# treiber.net
KiCad netlist of a schematic drawn in EAGLE
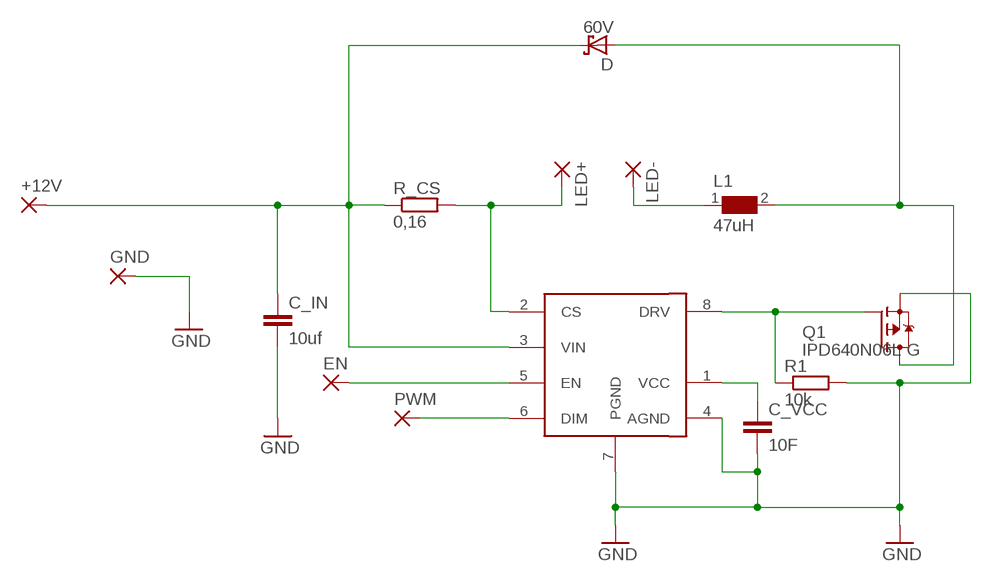
[diagram p0: schematic, sheet 1]

(export (version "E")
  (design (tool "Eeschema 10.0.6"))
  (components
    (comp (ref "+12V")
      (value "WIREPADSMD5-2,5")
      (footprint "eagle-import:5-2,5")
      (libsource (lib "eagle-import") (part "WIREPADSMD5-2,5"))
    )
    (comp (ref "C_IN")
      (value "10uf")
      (footprint "eagle-import:C1210")
      (libsource (lib "eagle-import") (part "C-EUC1210"))
    )
    (comp (ref "C_VCC")
      (value "10F")
      (footprint "eagle-import:C1210")
      (libsource (lib "eagle-import") (part "C-EUC1210"))
    )
    (comp (ref "D")
      (value "60V")
      (footprint "eagle-import:SMC")
      (libsource (lib "eagle-import") (part "SCHOTTKY-DIODESMC"))
    )
    (comp (ref "EN")
      (value "WIREPADSMD5-2,5")
      (footprint "eagle-import:5-2,5")
      (libsource (lib "eagle-import") (part "WIREPADSMD5-2,5"))
    )
    (comp (ref "GND")
      (value "WIREPADSMD5-2,5")
      (footprint "eagle-import:5-2,5")
      (libsource (lib "eagle-import") (part "WIREPADSMD5-2,5"))
    )
    (comp (ref "L1")
      (value "47uH")
      (footprint "eagle-import:WE-TPC_1028_1038")
      (fields (field (name "MPN") "744066680"))
      (libsource (lib "eagle-import") (part "WE-TPC_1028/1038-744066680"))
    )
    (comp (ref "LED+")
      (value "WIREPADSMD5-2,5")
      (footprint "eagle-import:5-2,5")
      (libsource (lib "eagle-import") (part "WIREPADSMD5-2,5"))
    )
    (comp (ref "LED-")
      (value "WIREPADSMD5-2,5")
      (footprint "eagle-import:5-2,5")
      (libsource (lib "eagle-import") (part "WIREPADSMD5-2,5"))
    )
    (comp (ref "MIC3203")
      (value "MIC3203")
      (footprint "eagle-import:SO08")
      (libsource (lib "eagle-import") (part "MIC3203"))
    )
    (comp (ref "PWM")
      (value "WIREPADSMD5-2,5")
      (footprint "eagle-import:5-2,5")
      (libsource (lib "eagle-import") (part "WIREPADSMD5-2,5"))
    )
    (comp (ref "Q1")
      (value "IPD640N06L G")
      (footprint "eagle-import:TO252")
      (libsource (lib "eagle-import") (part "FDD4141TO252"))
    )
    (comp (ref "R1")
      (value "10k")
      (footprint "eagle-import:M1206")
      (libsource (lib "eagle-import") (part "R-EU_M1206"))
    )
    (comp (ref "R_CS")
      (value "0,16")
      (footprint "eagle-import:R0603")
      (libsource (lib "eagle-import") (part "R-EU_R0603"))
    )
  )
  (nets
    (net (code "1") (name "GND") (class "Default")
      (node (ref "C_IN") (pin "2") (pinfunction "2_2") (pintype "passive"))
      (node (ref "C_VCC") (pin "2") (pinfunction "2_2") (pintype "passive"))
      (node (ref "GND") (pin "1") (pinfunction "P_1") (pintype "passive"))
      (node (ref "MIC3203") (pin "4") (pinfunction "AGND_4") (pintype "bidirectional"))
      (node (ref "MIC3203") (pin "7") (pinfunction "PGND_7") (pintype "bidirectional"))
      (node (ref "Q1") (pin "2") (pinfunction "S_2") (pintype "passive"))
      (node (ref "R1") (pin "2") (pinfunction "2_2") (pintype "passive"))
    )
    (net (code "2") (name "Net-(+12V-P)") (class "Default")
      (node (ref "+12V") (pin "1") (pinfunction "P_1") (pintype "passive"))
      (node (ref "C_IN") (pin "1") (pinfunction "1_1") (pintype "passive"))
      (node (ref "D") (pin "C") (pinfunction "C_C") (pintype "passive"))
      (node (ref "MIC3203") (pin "3") (pinfunction "VIN_3") (pintype "bidirectional"))
      (node (ref "R_CS") (pin "1") (pinfunction "1_1") (pintype "passive"))
    )
    (net (code "3") (name "Net-(EN-P)") (class "Default")
      (node (ref "EN") (pin "1") (pinfunction "P_1") (pintype "passive"))
      (node (ref "MIC3203") (pin "5") (pinfunction "EN_5") (pintype "bidirectional"))
    )
    (net (code "4") (name "Net-(LED+-P)") (class "Default")
      (node (ref "LED+") (pin "1") (pinfunction "P_1") (pintype "passive"))
      (node (ref "MIC3203") (pin "2") (pinfunction "CS_2") (pintype "bidirectional"))
      (node (ref "R_CS") (pin "2") (pinfunction "2_2") (pintype "passive"))
    )
    (net (code "5") (name "Net-(LED--P)") (class "Default")
      (node (ref "L1") (pin "1") (pinfunction "1_1") (pintype "passive"))
      (node (ref "LED-") (pin "1") (pinfunction "P_1") (pintype "passive"))
    )
    (net (code "6") (name "Net-(MIC3203-DIM)") (class "Default")
      (node (ref "MIC3203") (pin "6") (pinfunction "DIM_6") (pintype "bidirectional"))
      (node (ref "PWM") (pin "1") (pinfunction "P_1") (pintype "passive"))
    )
    (net (code "7") (name "Net-(MIC3203-DRV)") (class "Default")
      (node (ref "MIC3203") (pin "8") (pinfunction "DRV_8") (pintype "bidirectional"))
      (node (ref "Q1") (pin "1") (pinfunction "G_1") (pintype "passive"))
      (node (ref "R1") (pin "1") (pinfunction "1_1") (pintype "passive"))
    )
    (net (code "8") (name "Net-(MIC3203-VCC)") (class "Default")
      (node (ref "C_VCC") (pin "1") (pinfunction "1_1") (pintype "passive"))
      (node (ref "MIC3203") (pin "1") (pinfunction "VCC_1") (pintype "bidirectional"))
    )
    (net (code "9") (name "Net-(Q1-D)") (class "Default")
      (node (ref "D") (pin "A") (pinfunction "A_A") (pintype "passive"))
      (node (ref "L1") (pin "2") (pinfunction "2_2") (pintype "passive"))
      (node (ref "Q1") (pin "3") (pinfunction "D_3") (pintype "passive"))
    )
  )
)
